# ResetRelays.net
KiCad netlist of a schematic drawn in Altium Designer
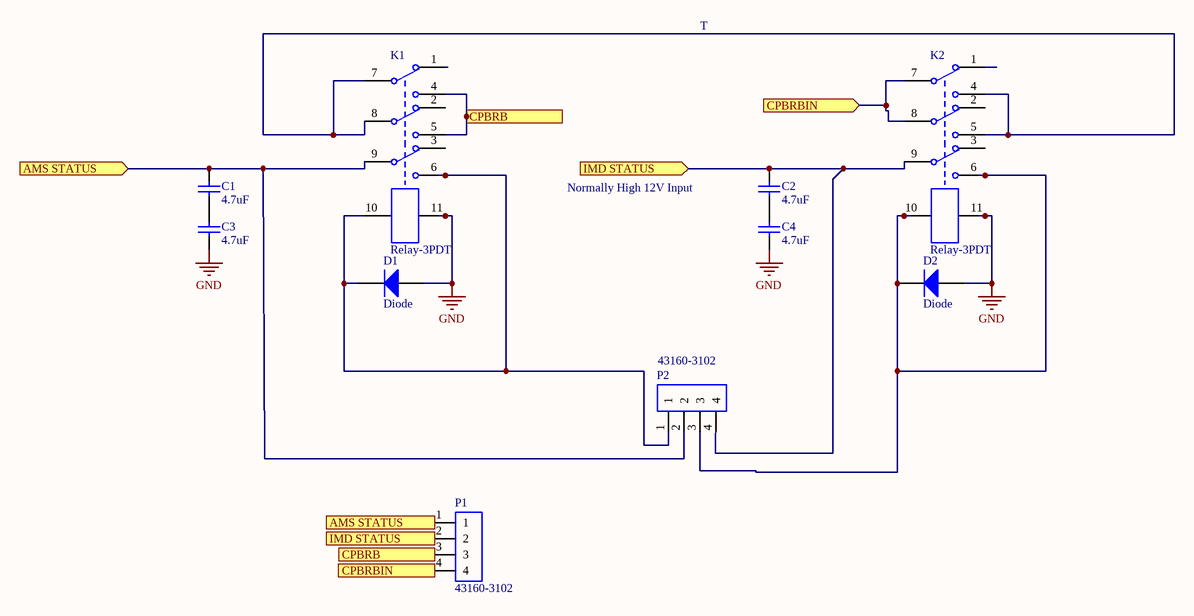
[diagram p0: ResetRelays.SchDoc]

(export (version "E")
  (design (tool "Eeschema 10.0.6"))
  (components
    (comp (ref "C1")
      (value "4.7uF")
      (footprint "CAPC3216X170N")
      (description "Capacitor (Semiconductor SIM Model)")
      (fields
        (field (name "MANUFACTURER") "Murata")
        (field (name "MANUFACTURER PART NUMBER") "GRM31MR71H105KA88L")
        (field (name "PUBLISHER") "Altium Limited")
      )
      (libsource (lib "Candunio") (part "Cap Semi"))
    )
    (comp (ref "C2")
      (value "4.7uF")
      (footprint "CAPC3216X170N")
      (description "Capacitor (Semiconductor SIM Model)")
      (fields
        (field (name "MANUFACTURER") "Murata")
        (field (name "MANUFACTURER PART NUMBER") "GRM31MR71H105KA88L")
        (field (name "PUBLISHER") "Altium Limited")
      )
      (libsource (lib "Candunio") (part "Cap Semi"))
    )
    (comp (ref "C3")
      (value "4.7uF")
      (footprint "CAPC3216X170N")
      (description "Capacitor (Semiconductor SIM Model)")
      (fields
        (field (name "MANUFACTURER") "Murata")
        (field (name "MANUFACTURER PART NUMBER") "GRM31MR71H105KA88L")
        (field (name "PUBLISHER") "Altium Limited")
      )
      (libsource (lib "Candunio") (part "Cap Semi"))
    )
    (comp (ref "C4")
      (value "4.7uF")
      (footprint "CAPC3216X170N")
      (description "Capacitor (Semiconductor SIM Model)")
      (fields
        (field (name "MANUFACTURER") "Murata")
        (field (name "MANUFACTURER PART NUMBER") "GRM31MR71H105KA88L")
        (field (name "PUBLISHER") "Altium Limited")
      )
      (libsource (lib "Candunio") (part "Cap Semi"))
    )
    (comp (ref "D1")
      (value "Diode")
      (footprint "DO-220AA")
      (description "Default Diode")
      (fields (field (name "PUBLISHER") "Altium Limited"))
      (libsource (lib "Candunio") (part "Diode"))
    )
    (comp (ref "D2")
      (value "Diode")
      (footprint "DO-220AA")
      (description "Default Diode")
      (fields (field (name "PUBLISHER") "Altium Limited"))
      (libsource (lib "Candunio") (part "Diode"))
    )
    (comp (ref "K1")
      (value "Relay-3PDT")
      (footprint "55.13")
      (libsource (lib "RESET circuit") (part "Relay-3PDT"))
    )
    (comp (ref "K2")
      (value "Relay-3PDT")
      (footprint "55.13")
      (libsource (lib "RESET circuit") (part "Relay-3PDT"))
    )
    (comp (ref "P1")
      (value "43160-3102")
      (footprint "431603102")
      (description "4pin blade header molex")
      (fields (field (name "RS PART NUMBER") "3639982P"))
      (libsource (lib "0431600104") (part "0431600104"))
    )
    (comp (ref "P2")
      (value "43160-3102")
      (footprint "431603102")
      (description "4pin blade header molex")
      (fields (field (name "RS PART NUMBER") "3639982P"))
      (libsource (lib "0431600104") (part "0431600104"))
    )
  )
  (nets
    (net (code "1") (name "/AMS STATUS") (class "Default")
      (node (ref "C1") (pin "2") (pinfunction "2_2") (pintype "passive"))
      (node (ref "K1") (pin "9") (pinfunction "9_9") (pintype "passive"))
      (node (ref "P1") (pin "1") (pinfunction "1_1") (pintype "passive"))
      (node (ref "P2") (pin "2") (pinfunction "2_2") (pintype "passive"))
    )
    (net (code "2") (name "/CPBRB") (class "Default")
      (node (ref "K1") (pin "4") (pinfunction "4_4") (pintype "passive"))
      (node (ref "K1") (pin "5") (pinfunction "5_5") (pintype "passive"))
      (node (ref "P1") (pin "3") (pinfunction "3_3") (pintype "passive"))
    )
    (net (code "3") (name "/CPBRBIN") (class "Default")
      (node (ref "K2") (pin "7") (pinfunction "7_7") (pintype "passive"))
      (node (ref "K2") (pin "8") (pinfunction "8_8") (pintype "passive"))
      (node (ref "P1") (pin "4") (pinfunction "4_4") (pintype "passive"))
    )
    (net (code "4") (name "/IMD STATUS") (class "Default")
      (node (ref "C2") (pin "2") (pinfunction "2_2") (pintype "passive"))
      (node (ref "K2") (pin "9") (pinfunction "9_9") (pintype "passive"))
      (node (ref "P1") (pin "2") (pinfunction "2_2") (pintype "passive"))
      (node (ref "P2") (pin "4") (pinfunction "4_4") (pintype "passive"))
    )
    (net (code "5") (name "GND") (class "Default")
      (node (ref "C3") (pin "1") (pinfunction "1_1") (pintype "passive"))
      (node (ref "C4") (pin "1") (pinfunction "1_1") (pintype "passive"))
      (node (ref "D1") (pin "1") (pinfunction "A_1") (pintype "passive"))
      (node (ref "D2") (pin "1") (pinfunction "A_1") (pintype "passive"))
      (node (ref "K1") (pin "11") (pinfunction "11_11") (pintype "passive"))
      (node (ref "K2") (pin "11") (pinfunction "11_11") (pintype "passive"))
    )
    (net (code "6") (name "Net-(C1-Pad1)") (class "Default")
      (node (ref "C1") (pin "1") (pinfunction "1_1") (pintype "passive"))
      (node (ref "C3") (pin "2") (pinfunction "2_2") (pintype "passive"))
    )
    (net (code "7") (name "Net-(C2-Pad1)") (class "Default")
      (node (ref "C2") (pin "1") (pinfunction "1_1") (pintype "passive"))
      (node (ref "C4") (pin "2") (pinfunction "2_2") (pintype "passive"))
    )
    (net (code "8") (name "Net-(D1-K)") (class "Default")
      (node (ref "D1") (pin "2") (pinfunction "K_2") (pintype "passive"))
      (node (ref "K1") (pin "10") (pinfunction "10_10") (pintype "passive"))
      (node (ref "K1") (pin "6") (pinfunction "6_6") (pintype "passive"))
      (node (ref "P2") (pin "1") (pinfunction "1_1") (pintype "passive"))
    )
    (net (code "9") (name "Net-(D2-K)") (class "Default")
      (node (ref "D2") (pin "2") (pinfunction "K_2") (pintype "passive"))
      (node (ref "K2") (pin "10") (pinfunction "10_10") (pintype "passive"))
      (node (ref "K2") (pin "6") (pinfunction "6_6") (pintype "passive"))
      (node (ref "P2") (pin "3") (pinfunction "3_3") (pintype "passive"))
    )
    (net (code "10") (name "Net-(K1-Pad7)") (class "Default")
      (node (ref "K1") (pin "7") (pinfunction "7_7") (pintype "passive"))
      (node (ref "K1") (pin "8") (pinfunction "8_8") (pintype "passive"))
      (node (ref "K2") (pin "4") (pinfunction "4_4") (pintype "passive"))
      (node (ref "K2") (pin "5") (pinfunction "5_5") (pintype "passive"))
    )
    (net (code "11") (name "unconnected-(K1-Pad1)") (class "Default")
      (node (ref "K1") (pin "1") (pinfunction "1_1") (pintype "passive"))
    )
    (net (code "12") (name "unconnected-(K1-Pad2)") (class "Default")
      (node (ref "K1") (pin "2") (pinfunction "2_2") (pintype "passive"))
    )
    (net (code "13") (name "unconnected-(K1-Pad3)") (class "Default")
      (node (ref "K1") (pin "3") (pinfunction "3_3") (pintype "passive"))
    )
    (net (code "14") (name "unconnected-(K2-Pad1)") (class "Default")
      (node (ref "K2") (pin "1") (pinfunction "1_1") (pintype "passive"))
    )
    (net (code "15") (name "unconnected-(K2-Pad2)") (class "Default")
      (node (ref "K2") (pin "2") (pinfunction "2_2") (pintype "passive"))
    )
    (net (code "16") (name "unconnected-(K2-Pad3)") (class "Default")
      (node (ref "K2") (pin "3") (pinfunction "3_3") (pintype "passive"))
    )
  )
)
